# wandercomputer.net
KiCad netlist of a schematic drawn in EAGLE
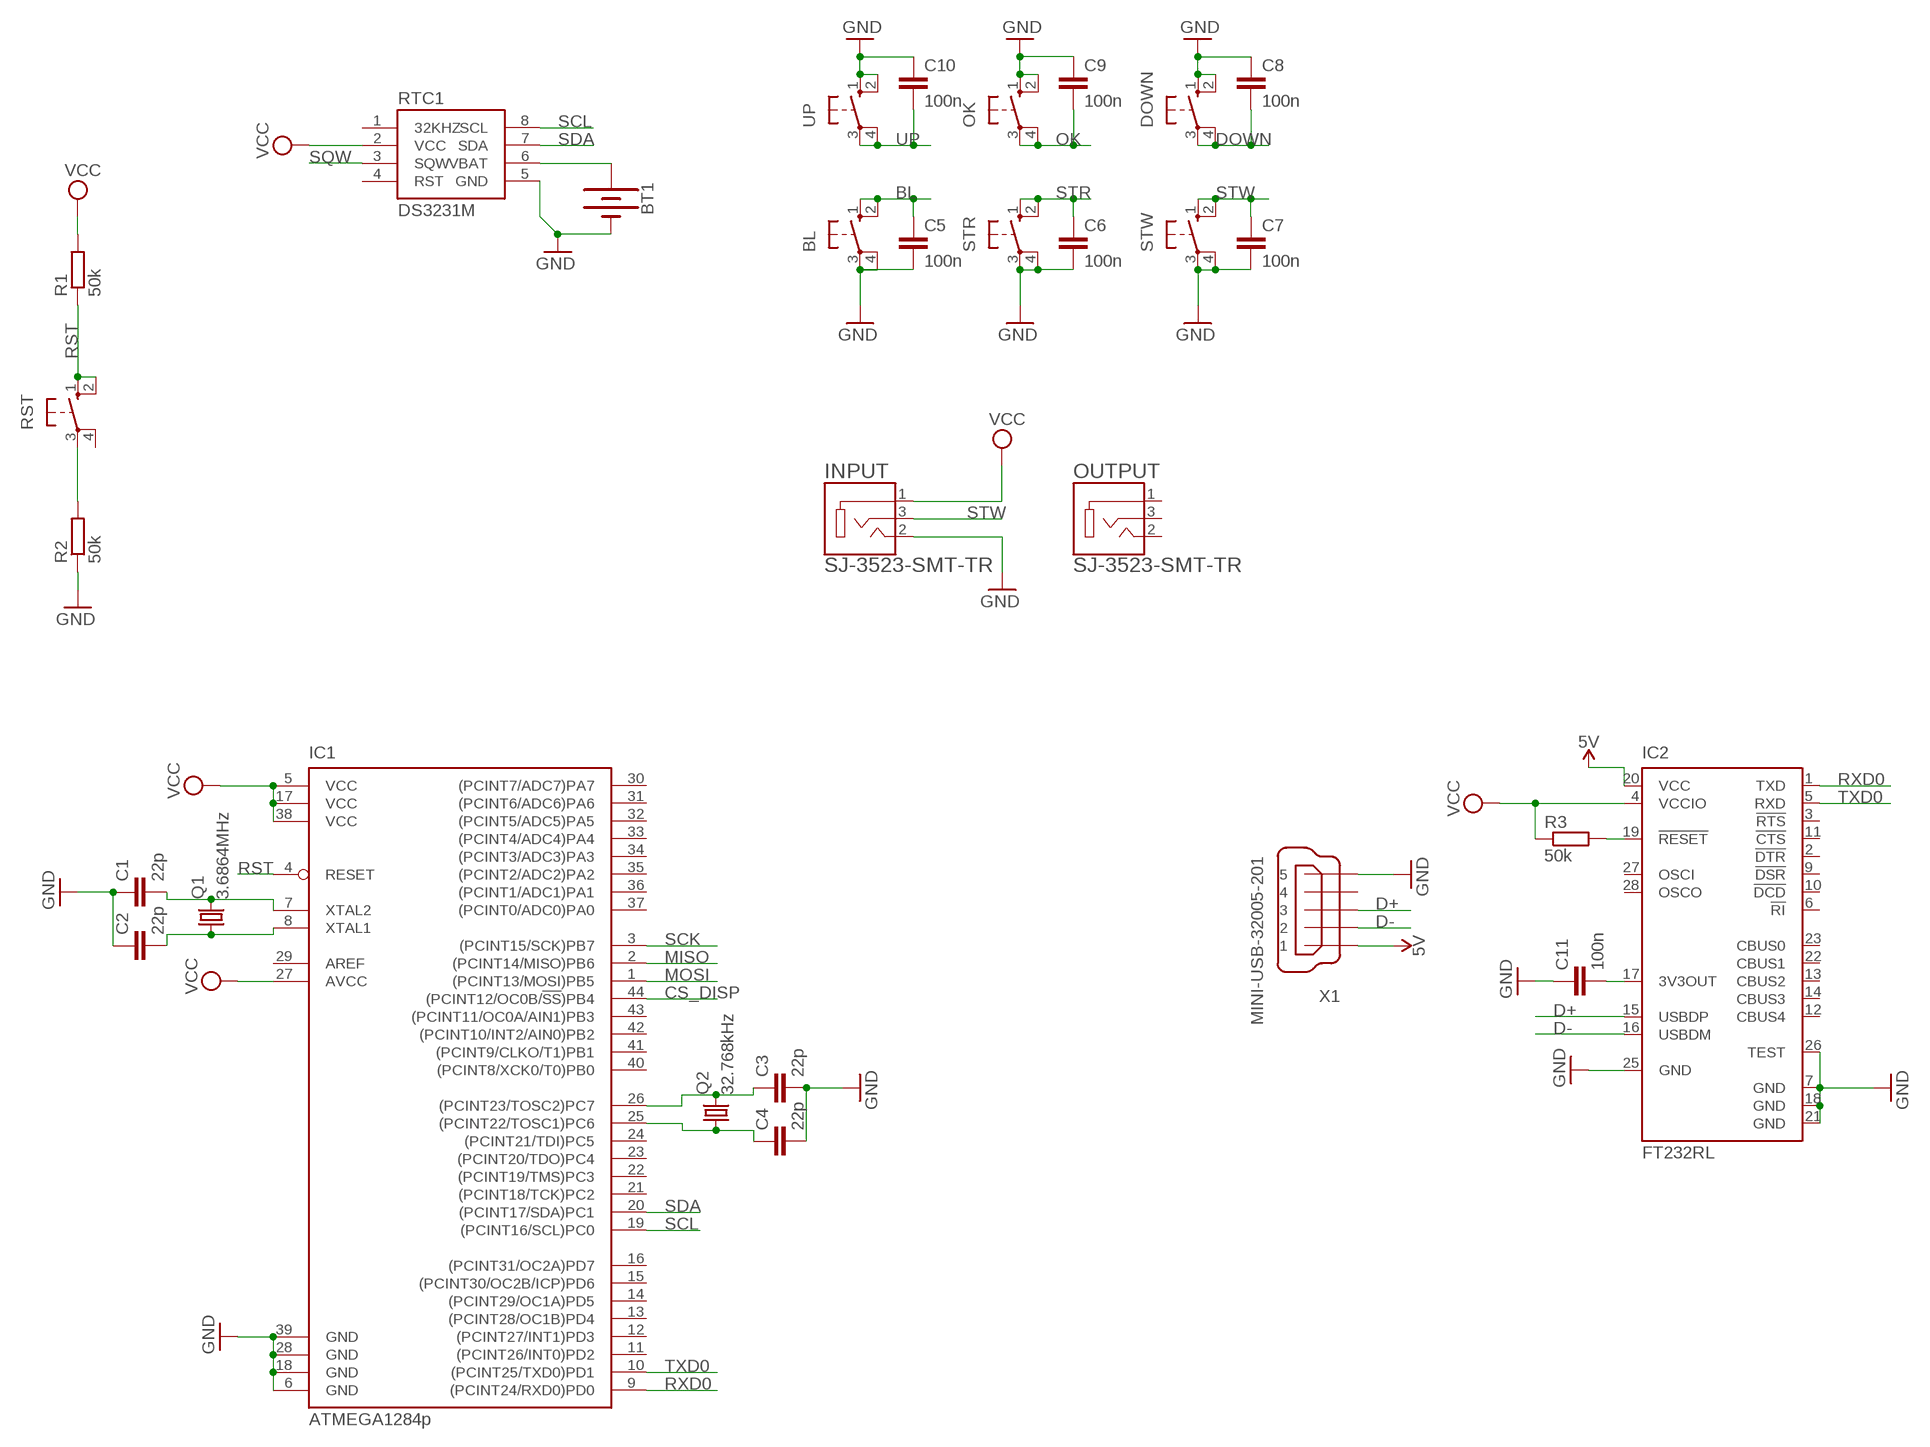
[diagram p0: schematic, sheet 1]

(export (version "E")
  (design (tool "Eeschema 10.0.6"))
  (components
    (comp (ref "BL")
      (value "10-XX")
      (footprint "eagle-import:B3F-10XX")
      (fields (field (name "MPN") "B3F-1000"))
      (libsource (lib "eagle-import") (part "10-XX"))
    )
    (comp (ref "BT1")
      (value "BATTERY-20MM_SMD")
      (footprint "eagle-import:BATTCON_20MM")
      (libsource (lib "eagle-import") (part "BATTERY-20MM_SMD"))
    )
    (comp (ref "C1")
      (value "22p")
      (footprint "eagle-import:C1808")
      (libsource (lib "eagle-import") (part "C-EUC1808"))
    )
    (comp (ref "C2")
      (value "22p")
      (footprint "eagle-import:C1808")
      (libsource (lib "eagle-import") (part "C-EUC1808"))
    )
    (comp (ref "C3")
      (value "22p")
      (footprint "eagle-import:C1808")
      (libsource (lib "eagle-import") (part "C-EUC1808"))
    )
    (comp (ref "C4")
      (value "22p")
      (footprint "eagle-import:C1808")
      (libsource (lib "eagle-import") (part "C-EUC1808"))
    )
    (comp (ref "C5")
      (value "100n")
      (footprint "eagle-import:C1808")
      (libsource (lib "eagle-import") (part "C-EUC1808"))
    )
    (comp (ref "C6")
      (value "100n")
      (footprint "eagle-import:C1808")
      (libsource (lib "eagle-import") (part "C-EUC1808"))
    )
    (comp (ref "C7")
      (value "100n")
      (footprint "eagle-import:C1808")
      (libsource (lib "eagle-import") (part "C-EUC1808"))
    )
    (comp (ref "C8")
      (value "100n")
      (footprint "eagle-import:C1808")
      (libsource (lib "eagle-import") (part "C-EUC1808"))
    )
    (comp (ref "C9")
      (value "100n")
      (footprint "eagle-import:C1808")
      (libsource (lib "eagle-import") (part "C-EUC1808"))
    )
    (comp (ref "C10")
      (value "100n")
      (footprint "eagle-import:C1808")
      (libsource (lib "eagle-import") (part "C-EUC1808"))
    )
    (comp (ref "C11")
      (value "100n")
      (footprint "eagle-import:C1808")
      (libsource (lib "eagle-import") (part "C-EUC1808"))
    )
    (comp (ref "DOWN")
      (value "10-XX")
      (footprint "eagle-import:B3F-10XX")
      (fields (field (name "MPN") "B3F-1000"))
      (libsource (lib "eagle-import") (part "10-XX"))
    )
    (comp (ref "IC1")
      (value "ATMEGA1284p")
      (footprint "eagle-import:TQFP44")
      (fields (field (name "MPN") "ATMEGA644PV-10AU"))
      (libsource (lib "eagle-import") (part "ATMEGA644A"))
    )
    (comp (ref "IC2")
      (value "FT232RL")
      (footprint "eagle-import:SSOP28")
      (libsource (lib "eagle-import") (part "FT232RL"))
    )
    (comp (ref "INPUT")
      (value "SJ-3523-SMT-TR")
      (footprint "eagle-import:CUI_SJ-3523-SMT-TR")
      (fields (field (name "MF") "CUI Inc"))
      (libsource (lib "eagle-import") (part "SJ-3523-SMT-TR"))
    )
    (comp (ref "OK")
      (value "10-XX")
      (footprint "eagle-import:B3F-10XX")
      (fields (field (name "MPN") "B3F-1000"))
      (libsource (lib "eagle-import") (part "10-XX"))
    )
    (comp (ref "OUTPUT")
      (value "SJ-3523-SMT-TR")
      (footprint "eagle-import:CUI_SJ-3523-SMT-TR")
      (fields (field (name "MF") "CUI Inc"))
      (libsource (lib "eagle-import") (part "SJ-3523-SMT-TR"))
    )
    (comp (ref "Q1")
      (value "3.6864MHz")
      (footprint "eagle-import:HC49U70")
      (libsource (lib "eagle-import") (part "CRYSTALHC49U70"))
    )
    (comp (ref "Q2")
      (value "32.768kHz")
      (footprint "eagle-import:TC26V")
      (libsource (lib "eagle-import") (part "CRYSTALTC26V"))
    )
    (comp (ref "R1")
      (value "50k")
      (footprint "eagle-import:R3216")
      (libsource (lib "eagle-import") (part "R-EU_R3216"))
    )
    (comp (ref "R2")
      (value "50k")
      (footprint "eagle-import:R3216")
      (libsource (lib "eagle-import") (part "R-EU_R3216"))
    )
    (comp (ref "R3")
      (value "50k")
      (footprint "eagle-import:R3216")
      (libsource (lib "eagle-import") (part "R-EU_R3216"))
    )
    (comp (ref "RST")
      (value "10-XX")
      (footprint "eagle-import:B3F-10XX")
      (fields (field (name "MPN") "B3F-1000"))
      (libsource (lib "eagle-import") (part "10-XX"))
    )
    (comp (ref "RTC1")
      (value "DS3231M")
      (footprint "eagle-import:SO08")
      (libsource (lib "eagle-import") (part "DS3231M"))
    )
    (comp (ref "STR")
      (value "10-XX")
      (footprint "eagle-import:B3F-10XX")
      (fields (field (name "MPN") "B3F-1000"))
      (libsource (lib "eagle-import") (part "10-XX"))
    )
    (comp (ref "STW")
      (value "10-XX")
      (footprint "eagle-import:B3F-10XX")
      (fields (field (name "MPN") "B3F-1000"))
      (libsource (lib "eagle-import") (part "10-XX"))
    )
    (comp (ref "UP")
      (value "10-XX")
      (footprint "eagle-import:B3F-10XX")
      (fields (field (name "MPN") "B3F-1000"))
      (libsource (lib "eagle-import") (part "10-XX"))
    )
    (comp (ref "X1")
      (value "MINI-USB-32005-201")
      (footprint "eagle-import:32005-201")
      (libsource (lib "eagle-import") (part "MINI-USB-32005-201"))
    )
  )
  (nets
    (net (code "1") (name "/BL") (class "Default")
      (node (ref "BL") (pin "1") (pinfunction "S_1") (pintype "passive"))
      (node (ref "BL") (pin "2") (pinfunction "S1_2") (pintype "passive"))
      (node (ref "C5") (pin "1") (pinfunction "1_1") (pintype "passive"))
    )
    (net (code "2") (name "/CS_DISP") (class "Default")
      (node (ref "IC1") (pin "44") (pinfunction "(PCINT12/OC0B/~{SS})PB4_44") (pintype "bidirectional"))
    )
    (net (code "3") (name "/D+") (class "Default")
      (node (ref "IC2") (pin "15") (pinfunction "USBDP_15") (pintype "bidirectional"))
      (node (ref "X1") (pin "3") (pinfunction "3_3") (pintype "passive"))
    )
    (net (code "4") (name "/D-") (class "Default")
      (node (ref "IC2") (pin "16") (pinfunction "USBDM_16") (pintype "bidirectional"))
      (node (ref "X1") (pin "2") (pinfunction "2_2") (pintype "passive"))
    )
    (net (code "5") (name "/DOWN") (class "Default")
      (node (ref "C8") (pin "2") (pinfunction "2_2") (pintype "passive"))
      (node (ref "DOWN") (pin "3") (pinfunction "P_3") (pintype "passive"))
      (node (ref "DOWN") (pin "4") (pinfunction "P1_4") (pintype "passive"))
    )
    (net (code "6") (name "/MISO") (class "Default")
      (node (ref "IC1") (pin "2") (pinfunction "(PCINT14/MISO)PB6_2") (pintype "bidirectional"))
    )
    (net (code "7") (name "/MOSI") (class "Default")
      (node (ref "IC1") (pin "1") (pinfunction "(PCINT13/MOSI)PB5_1") (pintype "bidirectional"))
    )
    (net (code "8") (name "/OK") (class "Default")
      (node (ref "C9") (pin "2") (pinfunction "2_2") (pintype "passive"))
      (node (ref "OK") (pin "3") (pinfunction "P_3") (pintype "passive"))
      (node (ref "OK") (pin "4") (pinfunction "P1_4") (pintype "passive"))
    )
    (net (code "9") (name "/RST") (class "Default")
      (node (ref "IC1") (pin "4") (pinfunction "RESET_4") (pintype "input"))
      (node (ref "R1") (pin "1") (pinfunction "1_1") (pintype "passive"))
      (node (ref "RST") (pin "1") (pinfunction "S_1") (pintype "passive"))
      (node (ref "RST") (pin "2") (pinfunction "S1_2") (pintype "passive"))
    )
    (net (code "10") (name "/RXD0") (class "Default")
      (node (ref "IC1") (pin "9") (pinfunction "(PCINT24/RXD0)PD0_9") (pintype "bidirectional"))
      (node (ref "IC2") (pin "1") (pinfunction "TXD_1") (pintype "output"))
    )
    (net (code "11") (name "/SCK") (class "Default")
      (node (ref "IC1") (pin "3") (pinfunction "(PCINT15/SCK)PB7_3") (pintype "bidirectional"))
    )
    (net (code "12") (name "/SCL") (class "Default")
      (node (ref "IC1") (pin "19") (pinfunction "(PCINT16/SCL)PC0_19") (pintype "output"))
      (node (ref "RTC1") (pin "8") (pinfunction "SCL_8") (pintype "bidirectional"))
    )
    (net (code "13") (name "/SDA") (class "Default")
      (node (ref "IC1") (pin "20") (pinfunction "(PCINT17/SDA)PC1_20") (pintype "output"))
      (node (ref "RTC1") (pin "7") (pinfunction "SDA_7") (pintype "bidirectional"))
    )
    (net (code "14") (name "/SQW") (class "Default")
      (node (ref "RTC1") (pin "3") (pinfunction "SQW_3") (pintype "output"))
    )
    (net (code "15") (name "/STR") (class "Default")
      (node (ref "C6") (pin "1") (pinfunction "1_1") (pintype "passive"))
      (node (ref "STR") (pin "1") (pinfunction "S_1") (pintype "passive"))
      (node (ref "STR") (pin "2") (pinfunction "S1_2") (pintype "passive"))
    )
    (net (code "16") (name "/STW") (class "Default")
      (node (ref "C7") (pin "1") (pinfunction "1_1") (pintype "passive"))
      (node (ref "INPUT") (pin "3") (pinfunction "3_3") (pintype "passive"))
      (node (ref "STW") (pin "1") (pinfunction "S_1") (pintype "passive"))
      (node (ref "STW") (pin "2") (pinfunction "S1_2") (pintype "passive"))
    )
    (net (code "17") (name "/TXD0") (class "Default")
      (node (ref "IC1") (pin "10") (pinfunction "(PCINT25/TXD0)PD1_10") (pintype "bidirectional"))
      (node (ref "IC2") (pin "5") (pinfunction "RXD_5") (pintype "input"))
    )
    (net (code "18") (name "/UP") (class "Default")
      (node (ref "C10") (pin "2") (pinfunction "2_2") (pintype "passive"))
      (node (ref "UP") (pin "3") (pinfunction "P_3") (pintype "passive"))
      (node (ref "UP") (pin "4") (pinfunction "P1_4") (pintype "passive"))
    )
    (net (code "19") (name "5V") (class "Default")
      (node (ref "IC2") (pin "20") (pinfunction "VCC_20") (pintype "power_in"))
      (node (ref "X1") (pin "1") (pinfunction "1_1") (pintype "passive"))
    )
    (net (code "20") (name "GND") (class "Default")
      (node (ref "BL") (pin "3") (pinfunction "P_3") (pintype "passive"))
      (node (ref "BL") (pin "4") (pinfunction "P1_4") (pintype "passive"))
      (node (ref "BT1") (pin "2") (pinfunction "-_2") (pintype "power_in"))
      (node (ref "C1") (pin "1") (pinfunction "1_1") (pintype "passive"))
      (node (ref "C10") (pin "1") (pinfunction "1_1") (pintype "passive"))
      (node (ref "C11") (pin "1") (pinfunction "1_1") (pintype "passive"))
      (node (ref "C2") (pin "1") (pinfunction "1_1") (pintype "passive"))
      (node (ref "C3") (pin "2") (pinfunction "2_2") (pintype "passive"))
      (node (ref "C4") (pin "2") (pinfunction "2_2") (pintype "passive"))
      (node (ref "C5") (pin "2") (pinfunction "2_2") (pintype "passive"))
      (node (ref "C6") (pin "2") (pinfunction "2_2") (pintype "passive"))
      (node (ref "C7") (pin "2") (pinfunction "2_2") (pintype "passive"))
      (node (ref "C8") (pin "1") (pinfunction "1_1") (pintype "passive"))
      (node (ref "C9") (pin "1") (pinfunction "1_1") (pintype "passive"))
      (node (ref "DOWN") (pin "1") (pinfunction "S_1") (pintype "passive"))
      (node (ref "DOWN") (pin "2") (pinfunction "S1_2") (pintype "passive"))
      (node (ref "IC1") (pin "18") (pinfunction "GND_18") (pintype "power_in"))
      (node (ref "IC1") (pin "28") (pinfunction "GND_28") (pintype "power_in"))
      (node (ref "IC1") (pin "39") (pinfunction "GND_39") (pintype "power_in"))
      (node (ref "IC1") (pin "6") (pinfunction "GND_6") (pintype "power_in"))
      (node (ref "IC2") (pin "18") (pinfunction "GND_18") (pintype "power_in"))
      (node (ref "IC2") (pin "21") (pinfunction "GND_21") (pintype "power_in"))
      (node (ref "IC2") (pin "25") (pinfunction "GND_25") (pintype "power_in"))
      (node (ref "IC2") (pin "26") (pinfunction "TEST_26") (pintype "input"))
      (node (ref "IC2") (pin "7") (pinfunction "GND_7") (pintype "power_in"))
      (node (ref "INPUT") (pin "2") (pinfunction "2_2") (pintype "passive"))
      (node (ref "OK") (pin "1") (pinfunction "S_1") (pintype "passive"))
      (node (ref "OK") (pin "2") (pinfunction "S1_2") (pintype "passive"))
      (node (ref "R2") (pin "1") (pinfunction "1_1") (pintype "passive"))
      (node (ref "RTC1") (pin "5") (pinfunction "GND_5") (pintype "power_in"))
      (node (ref "STR") (pin "3") (pinfunction "P_3") (pintype "passive"))
      (node (ref "STR") (pin "4") (pinfunction "P1_4") (pintype "passive"))
      (node (ref "STW") (pin "3") (pinfunction "P_3") (pintype "passive"))
      (node (ref "STW") (pin "4") (pinfunction "P1_4") (pintype "passive"))
      (node (ref "UP") (pin "1") (pinfunction "S_1") (pintype "passive"))
      (node (ref "UP") (pin "2") (pinfunction "S1_2") (pintype "passive"))
      (node (ref "X1") (pin "5") (pinfunction "5_5") (pintype "passive"))
    )
    (net (code "21") (name "Net-(BT1-+)") (class "Default")
      (node (ref "BT1") (pin "1") (pinfunction "+_1") (pintype "power_in"))
      (node (ref "RTC1") (pin "6") (pinfunction "VBAT_6") (pintype "power_in"))
    )
    (net (code "22") (name "Net-(IC1-(PCINT22{slash}TOSC1)PC6)") (class "Default")
      (node (ref "C4") (pin "1") (pinfunction "1_1") (pintype "passive"))
      (node (ref "IC1") (pin "25") (pinfunction "(PCINT22/TOSC1)PC6_25") (pintype "output"))
      (node (ref "Q2") (pin "1") (pinfunction "1_1") (pintype "passive"))
    )
    (net (code "23") (name "Net-(IC1-(PCINT23{slash}TOSC2)PC7)") (class "Default")
      (node (ref "C3") (pin "1") (pinfunction "1_1") (pintype "passive"))
      (node (ref "IC1") (pin "26") (pinfunction "(PCINT23/TOSC2)PC7_26") (pintype "output"))
      (node (ref "Q2") (pin "2") (pinfunction "2_2") (pintype "passive"))
    )
    (net (code "24") (name "Net-(IC1-XTAL1)") (class "Default")
      (node (ref "C2") (pin "2") (pinfunction "2_2") (pintype "passive"))
      (node (ref "IC1") (pin "8") (pinfunction "XTAL1_8") (pintype "bidirectional"))
      (node (ref "Q1") (pin "1") (pinfunction "1_1") (pintype "passive"))
    )
    (net (code "25") (name "Net-(IC1-XTAL2)") (class "Default")
      (node (ref "C1") (pin "2") (pinfunction "2_2") (pintype "passive"))
      (node (ref "IC1") (pin "7") (pinfunction "XTAL2_7") (pintype "bidirectional"))
      (node (ref "Q1") (pin "2") (pinfunction "2_2") (pintype "passive"))
    )
    (net (code "26") (name "Net-(IC2-3V3OUT)") (class "Default")
      (node (ref "C11") (pin "2") (pinfunction "2_2") (pintype "passive"))
      (node (ref "IC2") (pin "17") (pinfunction "3V3OUT_17") (pintype "output"))
    )
    (net (code "27") (name "Net-(IC2-~{RESET})") (class "Default")
      (node (ref "IC2") (pin "19") (pinfunction "~{RESET}_19") (pintype "input"))
      (node (ref "R3") (pin "2") (pinfunction "2_2") (pintype "passive"))
    )
    (net (code "28") (name "Net-(RST-P)") (class "Default")
      (node (ref "R2") (pin "2") (pinfunction "2_2") (pintype "passive"))
      (node (ref "RST") (pin "3") (pinfunction "P_3") (pintype "passive"))
    )
    (net (code "29") (name "VCC") (class "Default")
      (node (ref "IC1") (pin "17") (pinfunction "VCC_17") (pintype "power_in"))
      (node (ref "IC1") (pin "27") (pinfunction "AVCC_27") (pintype "power_in"))
      (node (ref "IC1") (pin "38") (pinfunction "VCC_38") (pintype "power_in"))
      (node (ref "IC1") (pin "5") (pinfunction "VCC_5") (pintype "power_in"))
      (node (ref "IC2") (pin "4") (pinfunction "VCCIO_4") (pintype "power_in"))
      (node (ref "INPUT") (pin "1") (pinfunction "1_1") (pintype "passive"))
      (node (ref "R1") (pin "2") (pinfunction "2_2") (pintype "passive"))
      (node (ref "R3") (pin "1") (pinfunction "1_1") (pintype "passive"))
      (node (ref "RTC1") (pin "2") (pinfunction "VCC_2") (pintype "power_in"))
    )
    (net (code "30") (name "unconnected-(IC1-(PCINT0{slash}ADC0)PA0-Pad37)") (class "Default")
      (node (ref "IC1") (pin "37") (pinfunction "(PCINT0/ADC0)PA0_37") (pintype "bidirectional"))
    )
    (net (code "31") (name "unconnected-(IC1-(PCINT1{slash}ADC1)PA1-Pad36)") (class "Default")
      (node (ref "IC1") (pin "36") (pinfunction "(PCINT1/ADC1)PA1_36") (pintype "bidirectional"))
    )
    (net (code "32") (name "unconnected-(IC1-(PCINT2{slash}ADC2)PA2-Pad35)") (class "Default")
      (node (ref "IC1") (pin "35") (pinfunction "(PCINT2/ADC2)PA2_35") (pintype "bidirectional"))
    )
    (net (code "33") (name "unconnected-(IC1-(PCINT3{slash}ADC3)PA3-Pad34)") (class "Default")
      (node (ref "IC1") (pin "34") (pinfunction "(PCINT3/ADC3)PA3_34") (pintype "bidirectional"))
    )
    (net (code "34") (name "unconnected-(IC1-(PCINT4{slash}ADC4)PA4-Pad33)") (class "Default")
      (node (ref "IC1") (pin "33") (pinfunction "(PCINT4/ADC4)PA4_33") (pintype "bidirectional"))
    )
    (net (code "35") (name "unconnected-(IC1-(PCINT5{slash}ADC5)PA5-Pad32)") (class "Default")
      (node (ref "IC1") (pin "32") (pinfunction "(PCINT5/ADC5)PA5_32") (pintype "bidirectional"))
    )
    (net (code "36") (name "unconnected-(IC1-(PCINT6{slash}ADC6)PA6-Pad31)") (class "Default")
      (node (ref "IC1") (pin "31") (pinfunction "(PCINT6/ADC6)PA6_31") (pintype "bidirectional"))
    )
    (net (code "37") (name "unconnected-(IC1-(PCINT7{slash}ADC7)PA7-Pad30)") (class "Default")
      (node (ref "IC1") (pin "30") (pinfunction "(PCINT7/ADC7)PA7_30") (pintype "bidirectional"))
    )
    (net (code "38") (name "unconnected-(IC1-(PCINT8{slash}XCK0{slash}T0)PB0-Pad40)") (class "Default")
      (node (ref "IC1") (pin "40") (pinfunction "(PCINT8/XCK0/T0)PB0_40") (pintype "bidirectional"))
    )
    (net (code "39") (name "unconnected-(IC1-(PCINT9{slash}CLKO{slash}T1)PB1-Pad41)") (class "Default")
      (node (ref "IC1") (pin "41") (pinfunction "(PCINT9/CLKO/T1)PB1_41") (pintype "bidirectional"))
    )
    (net (code "40") (name "unconnected-(IC1-(PCINT10{slash}INT2{slash}AIN0)PB2-Pad42)") (class "Default")
      (node (ref "IC1") (pin "42") (pinfunction "(PCINT10/INT2/AIN0)PB2_42") (pintype "bidirectional"))
    )
    (net (code "41") (name "unconnected-(IC1-(PCINT11{slash}OC0A{slash}AIN1)PB3-Pad43)") (class "Default")
      (node (ref "IC1") (pin "43") (pinfunction "(PCINT11/OC0A/AIN1)PB3_43") (pintype "bidirectional"))
    )
    (net (code "42") (name "unconnected-(IC1-(PCINT18{slash}TCK)PC2-Pad21)") (class "Default")
      (node (ref "IC1") (pin "21") (pinfunction "(PCINT18/TCK)PC2_21") (pintype "output"))
    )
    (net (code "43") (name "unconnected-(IC1-(PCINT19{slash}TMS)PC3-Pad22)") (class "Default")
      (node (ref "IC1") (pin "22") (pinfunction "(PCINT19/TMS)PC3_22") (pintype "output"))
    )
    (net (code "44") (name "unconnected-(IC1-(PCINT20{slash}TDO)PC4-Pad23)") (class "Default")
      (node (ref "IC1") (pin "23") (pinfunction "(PCINT20/TDO)PC4_23") (pintype "output"))
    )
    (net (code "45") (name "unconnected-(IC1-(PCINT21{slash}TDI)PC5-Pad24)") (class "Default")
      (node (ref "IC1") (pin "24") (pinfunction "(PCINT21/TDI)PC5_24") (pintype "output"))
    )
    (net (code "46") (name "unconnected-(IC1-(PCINT26{slash}INT0)PD2-Pad11)") (class "Default")
      (node (ref "IC1") (pin "11") (pinfunction "(PCINT26/INT0)PD2_11") (pintype "bidirectional"))
    )
    (net (code "47") (name "unconnected-(IC1-(PCINT27{slash}INT1)PD3-Pad12)") (class "Default")
      (node (ref "IC1") (pin "12") (pinfunction "(PCINT27/INT1)PD3_12") (pintype "bidirectional"))
    )
    (net (code "48") (name "unconnected-(IC1-(PCINT28{slash}OC1B)PD4-Pad13)") (class "Default")
      (node (ref "IC1") (pin "13") (pinfunction "(PCINT28/OC1B)PD4_13") (pintype "bidirectional"))
    )
    (net (code "49") (name "unconnected-(IC1-(PCINT29{slash}OC1A)PD5-Pad14)") (class "Default")
      (node (ref "IC1") (pin "14") (pinfunction "(PCINT29/OC1A)PD5_14") (pintype "bidirectional"))
    )
    (net (code "50") (name "unconnected-(IC1-(PCINT30{slash}OC2B{slash}ICP)PD6-Pad15)") (class "Default")
      (node (ref "IC1") (pin "15") (pinfunction "(PCINT30/OC2B/ICP)PD6_15") (pintype "bidirectional"))
    )
    (net (code "51") (name "unconnected-(IC1-(PCINT31{slash}OC2A)PD7-Pad16)") (class "Default")
      (node (ref "IC1") (pin "16") (pinfunction "(PCINT31/OC2A)PD7_16") (pintype "bidirectional"))
    )
    (net (code "52") (name "unconnected-(IC1-AREF-Pad29)") (class "Default")
      (node (ref "IC1") (pin "29") (pinfunction "AREF_29") (pintype "passive"))
    )
    (net (code "53") (name "unconnected-(IC2-CBUS0-Pad23)") (class "Default")
      (node (ref "IC2") (pin "23") (pinfunction "CBUS0_23") (pintype "bidirectional"))
    )
    (net (code "54") (name "unconnected-(IC2-CBUS1-Pad22)") (class "Default")
      (node (ref "IC2") (pin "22") (pinfunction "CBUS1_22") (pintype "bidirectional"))
    )
    (net (code "55") (name "unconnected-(IC2-CBUS2-Pad13)") (class "Default")
      (node (ref "IC2") (pin "13") (pinfunction "CBUS2_13") (pintype "bidirectional"))
    )
    (net (code "56") (name "unconnected-(IC2-CBUS3-Pad14)") (class "Default")
      (node (ref "IC2") (pin "14") (pinfunction "CBUS3_14") (pintype "bidirectional"))
    )
    (net (code "57") (name "unconnected-(IC2-CBUS4-Pad12)") (class "Default")
      (node (ref "IC2") (pin "12") (pinfunction "CBUS4_12") (pintype "bidirectional"))
    )
    (net (code "58") (name "unconnected-(IC2-OSCI-Pad27)") (class "Default")
      (node (ref "IC2") (pin "27") (pinfunction "OSCI_27") (pintype "input"))
    )
    (net (code "59") (name "unconnected-(IC2-OSCO-Pad28)") (class "Default")
      (node (ref "IC2") (pin "28") (pinfunction "OSCO_28") (pintype "output"))
    )
    (net (code "60") (name "unconnected-(IC2-~{CTS}-Pad11)") (class "Default")
      (node (ref "IC2") (pin "11") (pinfunction "~{CTS}_11") (pintype "input"))
    )
    (net (code "61") (name "unconnected-(IC2-~{DCD}-Pad10)") (class "Default")
      (node (ref "IC2") (pin "10") (pinfunction "~{DCD}_10") (pintype "input"))
    )
    (net (code "62") (name "unconnected-(IC2-~{DSR}-Pad9)") (class "Default")
      (node (ref "IC2") (pin "9") (pinfunction "~{DSR}_9") (pintype "input"))
    )
    (net (code "63") (name "unconnected-(IC2-~{DTR}-Pad2)") (class "Default")
      (node (ref "IC2") (pin "2") (pinfunction "~{DTR}_2") (pintype "output"))
    )
    (net (code "64") (name "unconnected-(IC2-~{RI}-Pad6)") (class "Default")
      (node (ref "IC2") (pin "6") (pinfunction "~{RI}_6") (pintype "input"))
    )
    (net (code "65") (name "unconnected-(IC2-~{RTS}-Pad3)") (class "Default")
      (node (ref "IC2") (pin "3") (pinfunction "~{RTS}_3") (pintype "output"))
    )
    (net (code "66") (name "unconnected-(OUTPUT-Pad1)") (class "Default")
      (node (ref "OUTPUT") (pin "1") (pinfunction "1_1") (pintype "passive"))
    )
    (net (code "67") (name "unconnected-(OUTPUT-Pad2)") (class "Default")
      (node (ref "OUTPUT") (pin "2") (pinfunction "2_2") (pintype "passive"))
    )
    (net (code "68") (name "unconnected-(OUTPUT-Pad3)") (class "Default")
      (node (ref "OUTPUT") (pin "3") (pinfunction "3_3") (pintype "passive"))
    )
    (net (code "69") (name "unconnected-(RST-P1-Pad4)") (class "Default")
      (node (ref "RST") (pin "4") (pinfunction "P1_4") (pintype "passive"))
    )
    (net (code "70") (name "unconnected-(RTC1-32KHZ-Pad1)") (class "Default")
      (node (ref "RTC1") (pin "1") (pinfunction "32KHZ_1") (pintype "output"))
    )
    (net (code "71") (name "unconnected-(RTC1-RST-Pad4)") (class "Default")
      (node (ref "RTC1") (pin "4") (pinfunction "RST_4") (pintype "bidirectional"))
    )
    (net (code "72") (name "unconnected-(X1-Pad4)") (class "Default")
      (node (ref "X1") (pin "4") (pinfunction "4_4") (pintype "passive"))
    )
  )
)
